# 4portHub.net
KiCad netlist of a schematic drawn in EAGLE
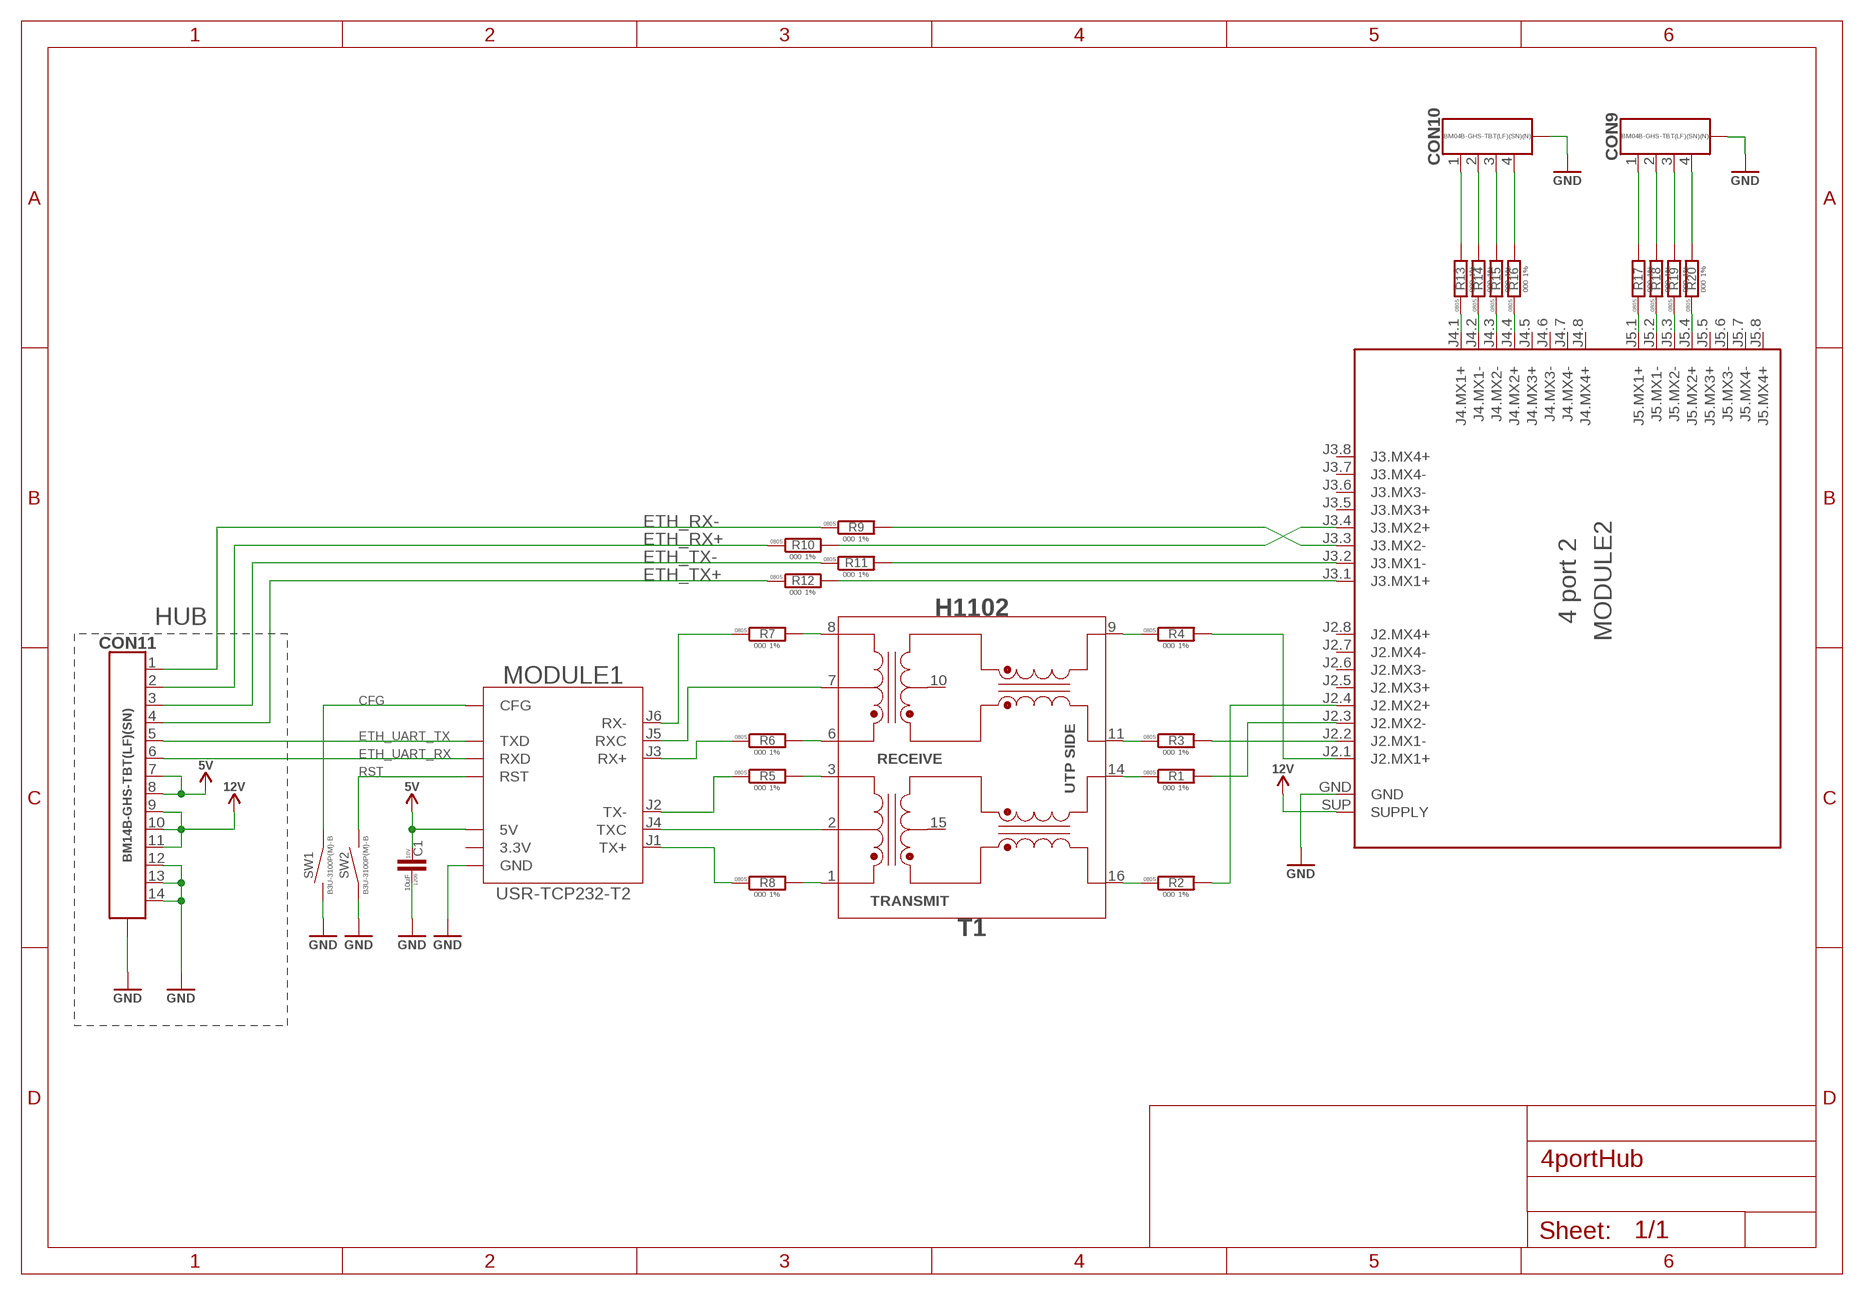
[diagram p0: schematic, sheet 1]

(export (version "E")
  (design (tool "Eeschema 10.0.6"))
  (components
    (comp (ref "C1")
      (value "10uF")
      (footprint "eagle-import:C1206")
      (fields (field (name "PACKAGE") "1206") (field (name "VOLTAGE") "10V"))
      (libsource (lib "eagle-import") (part "C-1206"))
    )
    (comp (ref "CON9")
      (value "CON-4P-TABS-JST-GH-TOP")
      (footprint "eagle-import:BM04B-GHS-TB")
      (fields (field (name "MANF#") "BM04B-GHS-TBT(LF)(SN)(N)") (field (name "MANF") "JST Sales America Inc"))
      (libsource (lib "eagle-import") (part "CON-4P-TABS-JST-GH-TOP"))
    )
    (comp (ref "CON10")
      (value "CON-4P-TABS-JST-GH-TOP")
      (footprint "eagle-import:BM04B-GHS-TB")
      (fields (field (name "MANF#") "BM04B-GHS-TBT(LF)(SN)(N)") (field (name "MANF") "JST Sales America Inc"))
      (libsource (lib "eagle-import") (part "CON-4P-TABS-JST-GH-TOP"))
    )
    (comp (ref "CON11")
      (value "CON-14P-TABS-JST-GH-TOP")
      (footprint "eagle-import:BM14B-GHS-TBT")
      (fields (field (name "MANF#") "BM14B-GHS-TBT(LF)(SN)") (field (name "MANF") "JST Sales America"))
      (libsource (lib "eagle-import") (part "CON-14P-TABS-JST-GH-TOP"))
    )
    (comp (ref "MODULE1")
      (value "USR-TCP232-T2")
      (footprint "eagle-import:USR-TCP232-T2")
      (fields (field (name "MANF#") "USR-TCP232-T2") (field (name "MANF") "Waveshare"))
      (libsource (lib "eagle-import") (part "USR-TCP232-T2"))
    )
    (comp (ref "MODULE2")
      (value "ANDDEAR_4PORT2")
      (footprint "eagle-import:ANDDEAR_4PORT2")
      (fields (field (name "MANF#") "4 port 2") (field (name "MANF") "ANDDEAR"))
      (libsource (lib "eagle-import") (part "ANDDEAR_4PORT2"))
    )
    (comp (ref "R1")
      (value "000")
      (footprint "eagle-import:R0805")
      (fields (field (name "PACKAGE") "0805") (field (name "TOLERANCE") "1%"))
      (libsource (lib "eagle-import") (part "R-0805-1%"))
    )
    (comp (ref "R2")
      (value "000")
      (footprint "eagle-import:R0805")
      (fields (field (name "PACKAGE") "0805") (field (name "TOLERANCE") "1%"))
      (libsource (lib "eagle-import") (part "R-0805-1%"))
    )
    (comp (ref "R3")
      (value "000")
      (footprint "eagle-import:R0805")
      (fields (field (name "PACKAGE") "0805") (field (name "TOLERANCE") "1%"))
      (libsource (lib "eagle-import") (part "R-0805-1%"))
    )
    (comp (ref "R4")
      (value "000")
      (footprint "eagle-import:R0805")
      (fields (field (name "PACKAGE") "0805") (field (name "TOLERANCE") "1%"))
      (libsource (lib "eagle-import") (part "R-0805-1%"))
    )
    (comp (ref "R5")
      (value "000")
      (footprint "eagle-import:R0805")
      (fields (field (name "PACKAGE") "0805") (field (name "TOLERANCE") "1%"))
      (libsource (lib "eagle-import") (part "R-0805-1%"))
    )
    (comp (ref "R6")
      (value "000")
      (footprint "eagle-import:R0805")
      (fields (field (name "PACKAGE") "0805") (field (name "TOLERANCE") "1%"))
      (libsource (lib "eagle-import") (part "R-0805-1%"))
    )
    (comp (ref "R7")
      (value "000")
      (footprint "eagle-import:R0805")
      (fields (field (name "PACKAGE") "0805") (field (name "TOLERANCE") "1%"))
      (libsource (lib "eagle-import") (part "R-0805-1%"))
    )
    (comp (ref "R8")
      (value "000")
      (footprint "eagle-import:R0805")
      (fields (field (name "PACKAGE") "0805") (field (name "TOLERANCE") "1%"))
      (libsource (lib "eagle-import") (part "R-0805-1%"))
    )
    (comp (ref "R9")
      (value "000")
      (footprint "eagle-import:R0805")
      (fields (field (name "PACKAGE") "0805") (field (name "TOLERANCE") "1%"))
      (libsource (lib "eagle-import") (part "R-0805-1%"))
    )
    (comp (ref "R10")
      (value "000")
      (footprint "eagle-import:R0805")
      (fields (field (name "PACKAGE") "0805") (field (name "TOLERANCE") "1%"))
      (libsource (lib "eagle-import") (part "R-0805-1%"))
    )
    (comp (ref "R11")
      (value "000")
      (footprint "eagle-import:R0805")
      (fields (field (name "PACKAGE") "0805") (field (name "TOLERANCE") "1%"))
      (libsource (lib "eagle-import") (part "R-0805-1%"))
    )
    (comp (ref "R12")
      (value "000")
      (footprint "eagle-import:R0805")
      (fields (field (name "PACKAGE") "0805") (field (name "TOLERANCE") "1%"))
      (libsource (lib "eagle-import") (part "R-0805-1%"))
    )
    (comp (ref "R13")
      (value "000")
      (footprint "eagle-import:R0805")
      (fields (field (name "PACKAGE") "0805") (field (name "TOLERANCE") "1%"))
      (libsource (lib "eagle-import") (part "R-0805-1%"))
    )
    (comp (ref "R14")
      (value "000")
      (footprint "eagle-import:R0805")
      (fields (field (name "PACKAGE") "0805") (field (name "TOLERANCE") "1%"))
      (libsource (lib "eagle-import") (part "R-0805-1%"))
    )
    (comp (ref "R15")
      (value "000")
      (footprint "eagle-import:R0805")
      (fields (field (name "PACKAGE") "0805") (field (name "TOLERANCE") "1%"))
      (libsource (lib "eagle-import") (part "R-0805-1%"))
    )
    (comp (ref "R16")
      (value "000")
      (footprint "eagle-import:R0805")
      (fields (field (name "PACKAGE") "0805") (field (name "TOLERANCE") "1%"))
      (libsource (lib "eagle-import") (part "R-0805-1%"))
    )
    (comp (ref "R17")
      (value "000")
      (footprint "eagle-import:R0805")
      (fields (field (name "PACKAGE") "0805") (field (name "TOLERANCE") "1%"))
      (libsource (lib "eagle-import") (part "R-0805-1%"))
    )
    (comp (ref "R18")
      (value "000")
      (footprint "eagle-import:R0805")
      (fields (field (name "PACKAGE") "0805") (field (name "TOLERANCE") "1%"))
      (libsource (lib "eagle-import") (part "R-0805-1%"))
    )
    (comp (ref "R19")
      (value "000")
      (footprint "eagle-import:R0805")
      (fields (field (name "PACKAGE") "0805") (field (name "TOLERANCE") "1%"))
      (libsource (lib "eagle-import") (part "R-0805-1%"))
    )
    (comp (ref "R20")
      (value "000")
      (footprint "eagle-import:R0805")
      (fields (field (name "PACKAGE") "0805") (field (name "TOLERANCE") "1%"))
      (libsource (lib "eagle-import") (part "R-0805-1%"))
    )
    (comp (ref "SW1")
      (value "TACT_SWITCH-B3U-3100P(M)-B")
      (footprint "eagle-import:B3U-3100P(M)-B")
      (fields (field (name "MANF") "OMRON"))
      (libsource (lib "eagle-import") (part "TACT_SWITCH-B3U-3100P(M)-B"))
    )
    (comp (ref "SW2")
      (value "TACT_SWITCH-B3U-3100P(M)-B")
      (footprint "eagle-import:B3U-3100P(M)-B")
      (fields (field (name "MANF") "OMRON"))
      (libsource (lib "eagle-import") (part "TACT_SWITCH-B3U-3100P(M)-B"))
    )
    (comp (ref "T1")
      (value "H1102NL")
      (footprint "eagle-import:H1102")
      (fields (field (name "MANF") "Pulse Electronics Corporation"))
      (libsource (lib "eagle-import") (part "H1102NL"))
    )
  )
  (nets
    (net (code "1") (name "/CFG") (class "Default")
      (node (ref "MODULE1") (pin "CFG") (pinfunction "CFG_CFG") (pintype "bidirectional"))
      (node (ref "SW1") (pin "P$1") (pinfunction "1_P$1") (pintype "bidirectional"))
    )
    (net (code "2") (name "/ETH_RX+") (class "Default")
      (node (ref "CON11") (pin "2") (pinfunction "2_2") (pintype "passive"))
      (node (ref "R10") (pin "1") (pinfunction "1_1") (pintype "passive"))
    )
    (net (code "3") (name "/ETH_RX-") (class "Default")
      (node (ref "CON11") (pin "1") (pinfunction "1_1") (pintype "passive"))
      (node (ref "R9") (pin "1") (pinfunction "1_1") (pintype "passive"))
    )
    (net (code "4") (name "/ETH_TX+") (class "Default")
      (node (ref "CON11") (pin "4") (pinfunction "4_4") (pintype "passive"))
      (node (ref "R12") (pin "1") (pinfunction "1_1") (pintype "passive"))
    )
    (net (code "5") (name "/ETH_TX-") (class "Default")
      (node (ref "CON11") (pin "3") (pinfunction "3_3") (pintype "passive"))
      (node (ref "R11") (pin "1") (pinfunction "1_1") (pintype "passive"))
    )
    (net (code "6") (name "/ETH_UART_RX") (class "Default")
      (node (ref "CON11") (pin "6") (pinfunction "6_6") (pintype "passive"))
      (node (ref "MODULE1") (pin "RXD") (pinfunction "RXD_RXD") (pintype "bidirectional"))
    )
    (net (code "7") (name "/ETH_UART_TX") (class "Default")
      (node (ref "CON11") (pin "5") (pinfunction "5_5") (pintype "passive"))
      (node (ref "MODULE1") (pin "TXD") (pinfunction "TXD_TXD") (pintype "bidirectional"))
    )
    (net (code "8") (name "/RST") (class "Default")
      (node (ref "MODULE1") (pin "RST") (pinfunction "RST_RST") (pintype "bidirectional"))
      (node (ref "SW2") (pin "P$2") (pinfunction "2_P$2") (pintype "bidirectional"))
    )
    (net (code "9") (name "5V") (class "Default")
      (node (ref "C1") (pin "P$2") (pinfunction "2_P$2") (pintype "passive"))
      (node (ref "CON11") (pin "7") (pinfunction "7_7") (pintype "passive"))
      (node (ref "CON11") (pin "8") (pinfunction "8_8") (pintype "passive"))
      (node (ref "MODULE1") (pin "5V") (pinfunction "5V_5V") (pintype "bidirectional"))
    )
    (net (code "10") (name "12V") (class "Default")
      (node (ref "CON11") (pin "10") (pinfunction "10_10") (pintype "passive"))
      (node (ref "CON11") (pin "11") (pinfunction "11_11") (pintype "passive"))
      (node (ref "CON11") (pin "9") (pinfunction "9_9") (pintype "passive"))
      (node (ref "MODULE2") (pin "SUP") (pinfunction "SUPPLY_SUP") (pintype "bidirectional"))
    )
    (net (code "11") (name "GND") (class "Default")
      (node (ref "C1") (pin "P$1") (pinfunction "1_P$1") (pintype "passive"))
      (node (ref "CON10") (pin "M$0") (pinfunction "GND_M$0") (pintype "bidirectional"))
      (node (ref "CON10") (pin "M$1") (pinfunction "GND_M$1") (pintype "bidirectional"))
      (node (ref "CON11") (pin "12") (pinfunction "12_12") (pintype "passive"))
      (node (ref "CON11") (pin "13") (pinfunction "13_13") (pintype "passive"))
      (node (ref "CON11") (pin "14") (pinfunction "14_14") (pintype "passive"))
      (node (ref "CON11") (pin "M$0") (pinfunction "G1_M$0") (pintype "passive"))
      (node (ref "CON11") (pin "M$1") (pinfunction "G1_M$1") (pintype "passive"))
      (node (ref "CON9") (pin "M$0") (pinfunction "GND_M$0") (pintype "bidirectional"))
      (node (ref "CON9") (pin "M$1") (pinfunction "GND_M$1") (pintype "bidirectional"))
      (node (ref "MODULE1") (pin "GND") (pinfunction "GND_GND") (pintype "bidirectional"))
      (node (ref "MODULE2") (pin "GND") (pinfunction "GND_GND") (pintype "bidirectional"))
      (node (ref "SW1") (pin "P$2") (pinfunction "2_P$2") (pintype "bidirectional"))
      (node (ref "SW2") (pin "P$1") (pinfunction "1_P$1") (pintype "bidirectional"))
    )
    (net (code "12") (name "Net-(CON9-Pad1)") (class "Default")
      (node (ref "CON9") (pin "1") (pinfunction "1_1") (pintype "bidirectional"))
      (node (ref "R17") (pin "2") (pinfunction "2_2") (pintype "passive"))
    )
    (net (code "13") (name "Net-(CON9-Pad2)") (class "Default")
      (node (ref "CON9") (pin "2") (pinfunction "2_2") (pintype "bidirectional"))
      (node (ref "R18") (pin "2") (pinfunction "2_2") (pintype "passive"))
    )
    (net (code "14") (name "Net-(CON9-Pad3)") (class "Default")
      (node (ref "CON9") (pin "3") (pinfunction "3_3") (pintype "bidirectional"))
      (node (ref "R19") (pin "2") (pinfunction "2_2") (pintype "passive"))
    )
    (net (code "15") (name "Net-(CON9-Pad4)") (class "Default")
      (node (ref "CON9") (pin "4") (pinfunction "4_4") (pintype "bidirectional"))
      (node (ref "R20") (pin "2") (pinfunction "2_2") (pintype "passive"))
    )
    (net (code "16") (name "Net-(CON10-Pad1)") (class "Default")
      (node (ref "CON10") (pin "1") (pinfunction "1_1") (pintype "bidirectional"))
      (node (ref "R13") (pin "2") (pinfunction "2_2") (pintype "passive"))
    )
    (net (code "17") (name "Net-(CON10-Pad2)") (class "Default")
      (node (ref "CON10") (pin "2") (pinfunction "2_2") (pintype "bidirectional"))
      (node (ref "R14") (pin "2") (pinfunction "2_2") (pintype "passive"))
    )
    (net (code "18") (name "Net-(CON10-Pad3)") (class "Default")
      (node (ref "CON10") (pin "3") (pinfunction "3_3") (pintype "bidirectional"))
      (node (ref "R15") (pin "2") (pinfunction "2_2") (pintype "passive"))
    )
    (net (code "19") (name "Net-(CON10-Pad4)") (class "Default")
      (node (ref "CON10") (pin "4") (pinfunction "4_4") (pintype "bidirectional"))
      (node (ref "R16") (pin "2") (pinfunction "2_2") (pintype "passive"))
    )
    (net (code "20") (name "Net-(MODULE1-RX+)") (class "Default")
      (node (ref "MODULE1") (pin "J3") (pinfunction "RX+_J3") (pintype "bidirectional"))
      (node (ref "R6") (pin "1") (pinfunction "1_1") (pintype "passive"))
    )
    (net (code "21") (name "Net-(MODULE1-RX-)") (class "Default")
      (node (ref "MODULE1") (pin "J6") (pinfunction "RX-_J6") (pintype "bidirectional"))
      (node (ref "R7") (pin "1") (pinfunction "1_1") (pintype "passive"))
    )
    (net (code "22") (name "Net-(MODULE1-RXC)") (class "Default")
      (node (ref "MODULE1") (pin "J5") (pinfunction "RXC_J5") (pintype "bidirectional"))
      (node (ref "T1") (pin "7") (pinfunction "7_7") (pintype "bidirectional"))
    )
    (net (code "23") (name "Net-(MODULE1-TX+)") (class "Default")
      (node (ref "MODULE1") (pin "J1") (pinfunction "TX+_J1") (pintype "bidirectional"))
      (node (ref "R8") (pin "1") (pinfunction "1_1") (pintype "passive"))
    )
    (net (code "24") (name "Net-(MODULE1-TX-)") (class "Default")
      (node (ref "MODULE1") (pin "J2") (pinfunction "TX-_J2") (pintype "bidirectional"))
      (node (ref "R5") (pin "1") (pinfunction "1_1") (pintype "passive"))
    )
    (net (code "25") (name "Net-(MODULE1-TXC)") (class "Default")
      (node (ref "MODULE1") (pin "J4") (pinfunction "TXC_J4") (pintype "bidirectional"))
      (node (ref "T1") (pin "2") (pinfunction "2_2") (pintype "bidirectional"))
    )
    (net (code "26") (name "Net-(MODULE2-J2.MX1+)") (class "Default")
      (node (ref "MODULE2") (pin "J2.1") (pinfunction "J2.MX1+_J2.1") (pintype "bidirectional"))
      (node (ref "R4") (pin "2") (pinfunction "2_2") (pintype "passive"))
    )
    (net (code "27") (name "Net-(MODULE2-J2.MX1-)") (class "Default")
      (node (ref "MODULE2") (pin "J2.2") (pinfunction "J2.MX1-_J2.2") (pintype "bidirectional"))
      (node (ref "R3") (pin "2") (pinfunction "2_2") (pintype "passive"))
    )
    (net (code "28") (name "Net-(MODULE2-J2.MX2+)") (class "Default")
      (node (ref "MODULE2") (pin "J2.4") (pinfunction "J2.MX2+_J2.4") (pintype "bidirectional"))
      (node (ref "R2") (pin "2") (pinfunction "2_2") (pintype "passive"))
    )
    (net (code "29") (name "Net-(MODULE2-J2.MX2-)") (class "Default")
      (node (ref "MODULE2") (pin "J2.3") (pinfunction "J2.MX2-_J2.3") (pintype "bidirectional"))
      (node (ref "R1") (pin "2") (pinfunction "2_2") (pintype "passive"))
    )
    (net (code "30") (name "Net-(MODULE2-J3.MX1+)") (class "Default")
      (node (ref "MODULE2") (pin "J3.1") (pinfunction "J3.MX1+_J3.1") (pintype "bidirectional"))
      (node (ref "R12") (pin "2") (pinfunction "2_2") (pintype "passive"))
    )
    (net (code "31") (name "Net-(MODULE2-J3.MX1-)") (class "Default")
      (node (ref "MODULE2") (pin "J3.2") (pinfunction "J3.MX1-_J3.2") (pintype "bidirectional"))
      (node (ref "R11") (pin "2") (pinfunction "2_2") (pintype "passive"))
    )
    (net (code "32") (name "Net-(MODULE2-J3.MX2+)") (class "Default")
      (node (ref "MODULE2") (pin "J3.4") (pinfunction "J3.MX2+_J3.4") (pintype "bidirectional"))
      (node (ref "R10") (pin "2") (pinfunction "2_2") (pintype "passive"))
    )
    (net (code "33") (name "Net-(MODULE2-J3.MX2-)") (class "Default")
      (node (ref "MODULE2") (pin "J3.3") (pinfunction "J3.MX2-_J3.3") (pintype "bidirectional"))
      (node (ref "R9") (pin "2") (pinfunction "2_2") (pintype "passive"))
    )
    (net (code "34") (name "Net-(MODULE2-J4.MX1+)") (class "Default")
      (node (ref "MODULE2") (pin "J4.1") (pinfunction "J4.MX1+_J4.1") (pintype "bidirectional"))
      (node (ref "R13") (pin "1") (pinfunction "1_1") (pintype "passive"))
    )
    (net (code "35") (name "Net-(MODULE2-J4.MX1-)") (class "Default")
      (node (ref "MODULE2") (pin "J4.2") (pinfunction "J4.MX1-_J4.2") (pintype "bidirectional"))
      (node (ref "R14") (pin "1") (pinfunction "1_1") (pintype "passive"))
    )
    (net (code "36") (name "Net-(MODULE2-J4.MX2+)") (class "Default")
      (node (ref "MODULE2") (pin "J4.4") (pinfunction "J4.MX2+_J4.4") (pintype "bidirectional"))
      (node (ref "R16") (pin "1") (pinfunction "1_1") (pintype "passive"))
    )
    (net (code "37") (name "Net-(MODULE2-J4.MX2-)") (class "Default")
      (node (ref "MODULE2") (pin "J4.3") (pinfunction "J4.MX2-_J4.3") (pintype "bidirectional"))
      (node (ref "R15") (pin "1") (pinfunction "1_1") (pintype "passive"))
    )
    (net (code "38") (name "Net-(MODULE2-J5.MX1+)") (class "Default")
      (node (ref "MODULE2") (pin "J5.1") (pinfunction "J5.MX1+_J5.1") (pintype "bidirectional"))
      (node (ref "R17") (pin "1") (pinfunction "1_1") (pintype "passive"))
    )
    (net (code "39") (name "Net-(MODULE2-J5.MX1-)") (class "Default")
      (node (ref "MODULE2") (pin "J5.2") (pinfunction "J5.MX1-_J5.2") (pintype "bidirectional"))
      (node (ref "R18") (pin "1") (pinfunction "1_1") (pintype "passive"))
    )
    (net (code "40") (name "Net-(MODULE2-J5.MX2+)") (class "Default")
      (node (ref "MODULE2") (pin "J5.4") (pinfunction "J5.MX2+_J5.4") (pintype "bidirectional"))
      (node (ref "R20") (pin "1") (pinfunction "1_1") (pintype "passive"))
    )
    (net (code "41") (name "Net-(MODULE2-J5.MX2-)") (class "Default")
      (node (ref "MODULE2") (pin "J5.3") (pinfunction "J5.MX2-_J5.3") (pintype "bidirectional"))
      (node (ref "R19") (pin "1") (pinfunction "1_1") (pintype "passive"))
    )
    (net (code "42") (name "Net-(R1-Pad1)") (class "Default")
      (node (ref "R1") (pin "1") (pinfunction "1_1") (pintype "passive"))
      (node (ref "T1") (pin "14") (pinfunction "14_14") (pintype "bidirectional"))
    )
    (net (code "43") (name "Net-(R2-Pad1)") (class "Default")
      (node (ref "R2") (pin "1") (pinfunction "1_1") (pintype "passive"))
      (node (ref "T1") (pin "16") (pinfunction "16_16") (pintype "bidirectional"))
    )
    (net (code "44") (name "Net-(R3-Pad1)") (class "Default")
      (node (ref "R3") (pin "1") (pinfunction "1_1") (pintype "passive"))
      (node (ref "T1") (pin "11") (pinfunction "11_11") (pintype "bidirectional"))
    )
    (net (code "45") (name "Net-(R4-Pad1)") (class "Default")
      (node (ref "R4") (pin "1") (pinfunction "1_1") (pintype "passive"))
      (node (ref "T1") (pin "9") (pinfunction "9_9") (pintype "bidirectional"))
    )
    (net (code "46") (name "Net-(R5-Pad2)") (class "Default")
      (node (ref "R5") (pin "2") (pinfunction "2_2") (pintype "passive"))
      (node (ref "T1") (pin "3") (pinfunction "3_3") (pintype "bidirectional"))
    )
    (net (code "47") (name "Net-(R6-Pad2)") (class "Default")
      (node (ref "R6") (pin "2") (pinfunction "2_2") (pintype "passive"))
      (node (ref "T1") (pin "6") (pinfunction "6_6") (pintype "bidirectional"))
    )
    (net (code "48") (name "Net-(R7-Pad2)") (class "Default")
      (node (ref "R7") (pin "2") (pinfunction "2_2") (pintype "passive"))
      (node (ref "T1") (pin "8") (pinfunction "8_8") (pintype "bidirectional"))
    )
    (net (code "49") (name "Net-(R8-Pad2)") (class "Default")
      (node (ref "R8") (pin "2") (pinfunction "2_2") (pintype "passive"))
      (node (ref "T1") (pin "1") (pinfunction "1_1") (pintype "bidirectional"))
    )
    (net (code "50") (name "unconnected-(MODULE1-Pad3.3V)") (class "Default")
      (node (ref "MODULE1") (pin "3.3V") (pinfunction "3.3V_3.3V") (pintype "bidirectional"))
    )
    (net (code "51") (name "unconnected-(MODULE2-J2.MX3+-PadJ2.5)") (class "Default")
      (node (ref "MODULE2") (pin "J2.5") (pinfunction "J2.MX3+_J2.5") (pintype "bidirectional"))
    )
    (net (code "52") (name "unconnected-(MODULE2-J2.MX3--PadJ2.6)") (class "Default")
      (node (ref "MODULE2") (pin "J2.6") (pinfunction "J2.MX3-_J2.6") (pintype "bidirectional"))
    )
    (net (code "53") (name "unconnected-(MODULE2-J2.MX4+-PadJ2.8)") (class "Default")
      (node (ref "MODULE2") (pin "J2.8") (pinfunction "J2.MX4+_J2.8") (pintype "bidirectional"))
    )
    (net (code "54") (name "unconnected-(MODULE2-J2.MX4--PadJ2.7)") (class "Default")
      (node (ref "MODULE2") (pin "J2.7") (pinfunction "J2.MX4-_J2.7") (pintype "bidirectional"))
    )
    (net (code "55") (name "unconnected-(MODULE2-J3.MX3+-PadJ3.5)") (class "Default")
      (node (ref "MODULE2") (pin "J3.5") (pinfunction "J3.MX3+_J3.5") (pintype "bidirectional"))
    )
    (net (code "56") (name "unconnected-(MODULE2-J3.MX3--PadJ3.6)") (class "Default")
      (node (ref "MODULE2") (pin "J3.6") (pinfunction "J3.MX3-_J3.6") (pintype "bidirectional"))
    )
    (net (code "57") (name "unconnected-(MODULE2-J3.MX4+-PadJ3.8)") (class "Default")
      (node (ref "MODULE2") (pin "J3.8") (pinfunction "J3.MX4+_J3.8") (pintype "bidirectional"))
    )
    (net (code "58") (name "unconnected-(MODULE2-J3.MX4--PadJ3.7)") (class "Default")
      (node (ref "MODULE2") (pin "J3.7") (pinfunction "J3.MX4-_J3.7") (pintype "bidirectional"))
    )
    (net (code "59") (name "unconnected-(MODULE2-J4.MX3+-PadJ4.5)") (class "Default")
      (node (ref "MODULE2") (pin "J4.5") (pinfunction "J4.MX3+_J4.5") (pintype "bidirectional"))
    )
    (net (code "60") (name "unconnected-(MODULE2-J4.MX3--PadJ4.6)") (class "Default")
      (node (ref "MODULE2") (pin "J4.6") (pinfunction "J4.MX3-_J4.6") (pintype "bidirectional"))
    )
    (net (code "61") (name "unconnected-(MODULE2-J4.MX4+-PadJ4.8)") (class "Default")
      (node (ref "MODULE2") (pin "J4.8") (pinfunction "J4.MX4+_J4.8") (pintype "bidirectional"))
    )
    (net (code "62") (name "unconnected-(MODULE2-J4.MX4--PadJ4.7)") (class "Default")
      (node (ref "MODULE2") (pin "J4.7") (pinfunction "J4.MX4-_J4.7") (pintype "bidirectional"))
    )
    (net (code "63") (name "unconnected-(MODULE2-J5.MX3+-PadJ5.5)") (class "Default")
      (node (ref "MODULE2") (pin "J5.5") (pinfunction "J5.MX3+_J5.5") (pintype "bidirectional"))
    )
    (net (code "64") (name "unconnected-(MODULE2-J5.MX3--PadJ5.6)") (class "Default")
      (node (ref "MODULE2") (pin "J5.6") (pinfunction "J5.MX3-_J5.6") (pintype "bidirectional"))
    )
    (net (code "65") (name "unconnected-(MODULE2-J5.MX4+-PadJ5.8)") (class "Default")
      (node (ref "MODULE2") (pin "J5.8") (pinfunction "J5.MX4+_J5.8") (pintype "bidirectional"))
    )
    (net (code "66") (name "unconnected-(MODULE2-J5.MX4--PadJ5.7)") (class "Default")
      (node (ref "MODULE2") (pin "J5.7") (pinfunction "J5.MX4-_J5.7") (pintype "bidirectional"))
    )
    (net (code "67") (name "unconnected-(T1-Pad10)") (class "Default")
      (node (ref "T1") (pin "10") (pinfunction "10_10") (pintype "bidirectional"))
    )
    (net (code "68") (name "unconnected-(T1-Pad15)") (class "Default")
      (node (ref "T1") (pin "15") (pinfunction "15_15") (pintype "bidirectional"))
    )
  )
)
